# Main_Sheet.net
KiCad netlist of a schematic drawn in Altium Designer
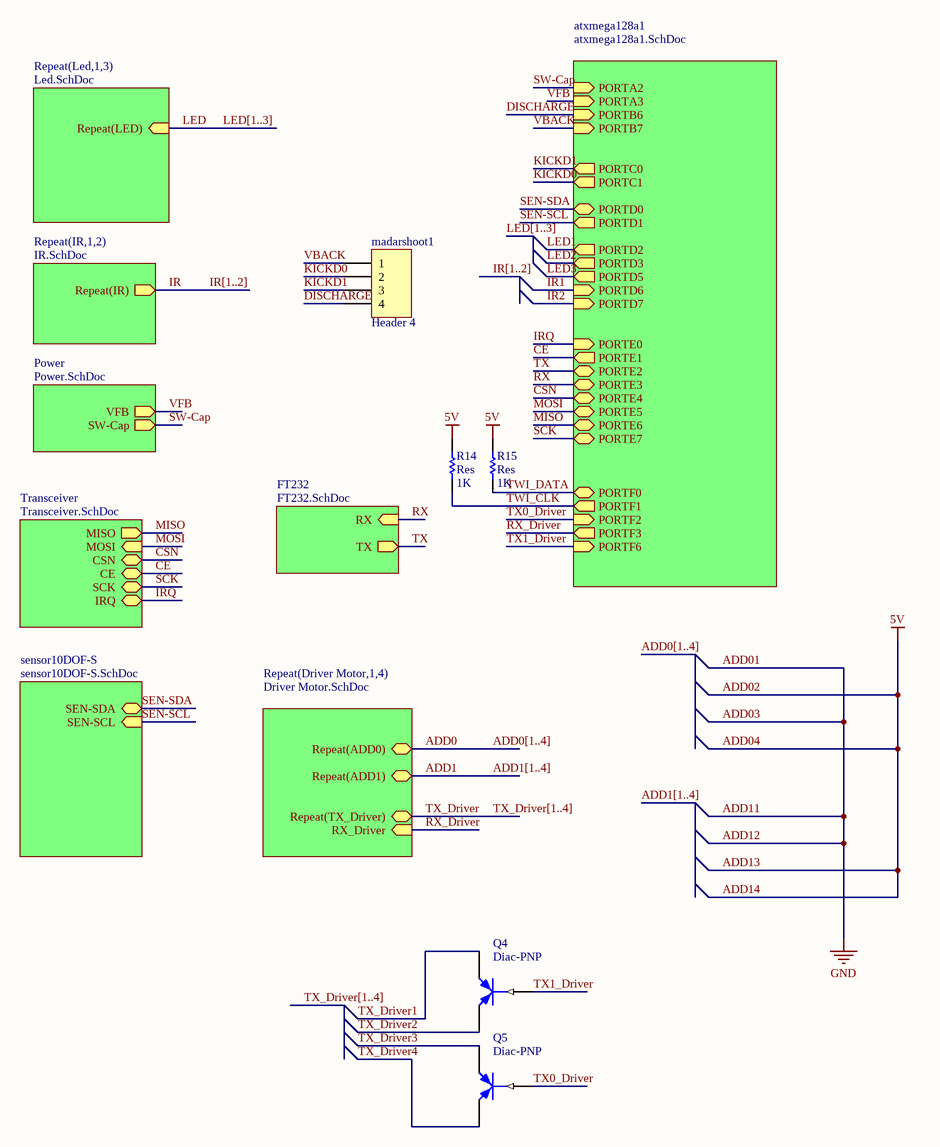
[diagram p0: Main Sheet.SchDoc]

(export (version "E")
  (design (tool "Eeschema 10.0.6"))
  (components
    (comp (ref "madarshoot1")
      (value "Header 4")
      (footprint "sucket-smd-4pin")
      (description "Header, 4-Pin")
      (fields (field (name "PUBLISHER") "Altium Limited"))
      (libsource (lib "KN2CLib") (part "Header 4"))
    )
    (comp (ref "Q4")
      (value "Diac-PNP")
      (footprint "Diode-comcathod")
      (description "DIAC")
      (fields (field (name "PUBLISHER") "Altium Limited"))
      (libsource (lib "Miscellaneous Devices") (part "Diac-PNP"))
    )
    (comp (ref "Q5")
      (value "Diac-PNP")
      (footprint "Diode-comcathod")
      (description "DIAC")
      (fields (field (name "PUBLISHER") "Altium Limited"))
      (libsource (lib "Miscellaneous Devices") (part "Diac-PNP"))
    )
    (comp (ref "R14")
      (value "Res")
      (footprint "2012[0805]")
      (description "Semiconductor Resistor")
      (fields (field (name "ALTIUM_VALUE") "1K") (field (name "PUBLISHER") "Altium Limited"))
      (libsource (lib "KN2CLib") (part "Res"))
    )
    (comp (ref "R15")
      (value "Res")
      (footprint "2012[0805]")
      (description "Semiconductor Resistor")
      (fields (field (name "ALTIUM_VALUE") "1K") (field (name "PUBLISHER") "Altium Limited"))
      (libsource (lib "KN2CLib") (part "Res"))
    )
  )
  (nets
    (net (code "7") (name "/DISCHARGE") (class "Default")
      (node (ref "madarshoot1") (pin "4") (pinfunction "4_4") (pintype "passive"))
    )
    (net (code "13") (name "/KICKD0") (class "Default")
      (node (ref "madarshoot1") (pin "2") (pinfunction "2_2") (pintype "passive"))
    )
    (net (code "14") (name "/KICKD1") (class "Default")
      (node (ref "madarshoot1") (pin "3") (pinfunction "3_3") (pintype "passive"))
    )
    (net (code "28") (name "/TWI_CLK") (class "Default")
      (node (ref "R14") (pin "1") (pinfunction "1_1") (pintype "passive"))
    )
    (net (code "29") (name "/TWI_DATA") (class "Default")
      (node (ref "R15") (pin "1") (pinfunction "1_1") (pintype "passive"))
    )
    (net (code "31") (name "/TX0_Driver") (class "Default")
      (node (ref "Q5") (pin "1") (pinfunction "B_1") (pintype "input"))
    )
    (net (code "32") (name "/TX1_Driver") (class "Default")
      (node (ref "Q4") (pin "1") (pinfunction "B_1") (pintype "input"))
    )
    (net (code "34") (name "/TX_Driver1") (class "Default")
      (node (ref "Q4") (pin "3") (pinfunction "C_3") (pintype "passive"))
    )
    (net (code "35") (name "/TX_Driver2") (class "Default")
      (node (ref "Q4") (pin "2") (pinfunction "E_2") (pintype "passive"))
    )
    (net (code "36") (name "/TX_Driver3") (class "Default")
      (node (ref "Q5") (pin "3") (pinfunction "C_3") (pintype "passive"))
    )
    (net (code "37") (name "/TX_Driver4") (class "Default")
      (node (ref "Q5") (pin "2") (pinfunction "E_2") (pintype "passive"))
    )
    (net (code "39") (name "/VBACK") (class "Default")
      (node (ref "madarshoot1") (pin "1") (pinfunction "1_1") (pintype "passive"))
    )
    (net (code "41") (name "5V") (class "Default")
      (node (ref "R14") (pin "2") (pinfunction "2_2") (pintype "passive"))
      (node (ref "R15") (pin "2") (pinfunction "2_2") (pintype "passive"))
    )
  )
)
